# Spannungsversorgung.net
KiCad netlist of a schematic drawn in EAGLE
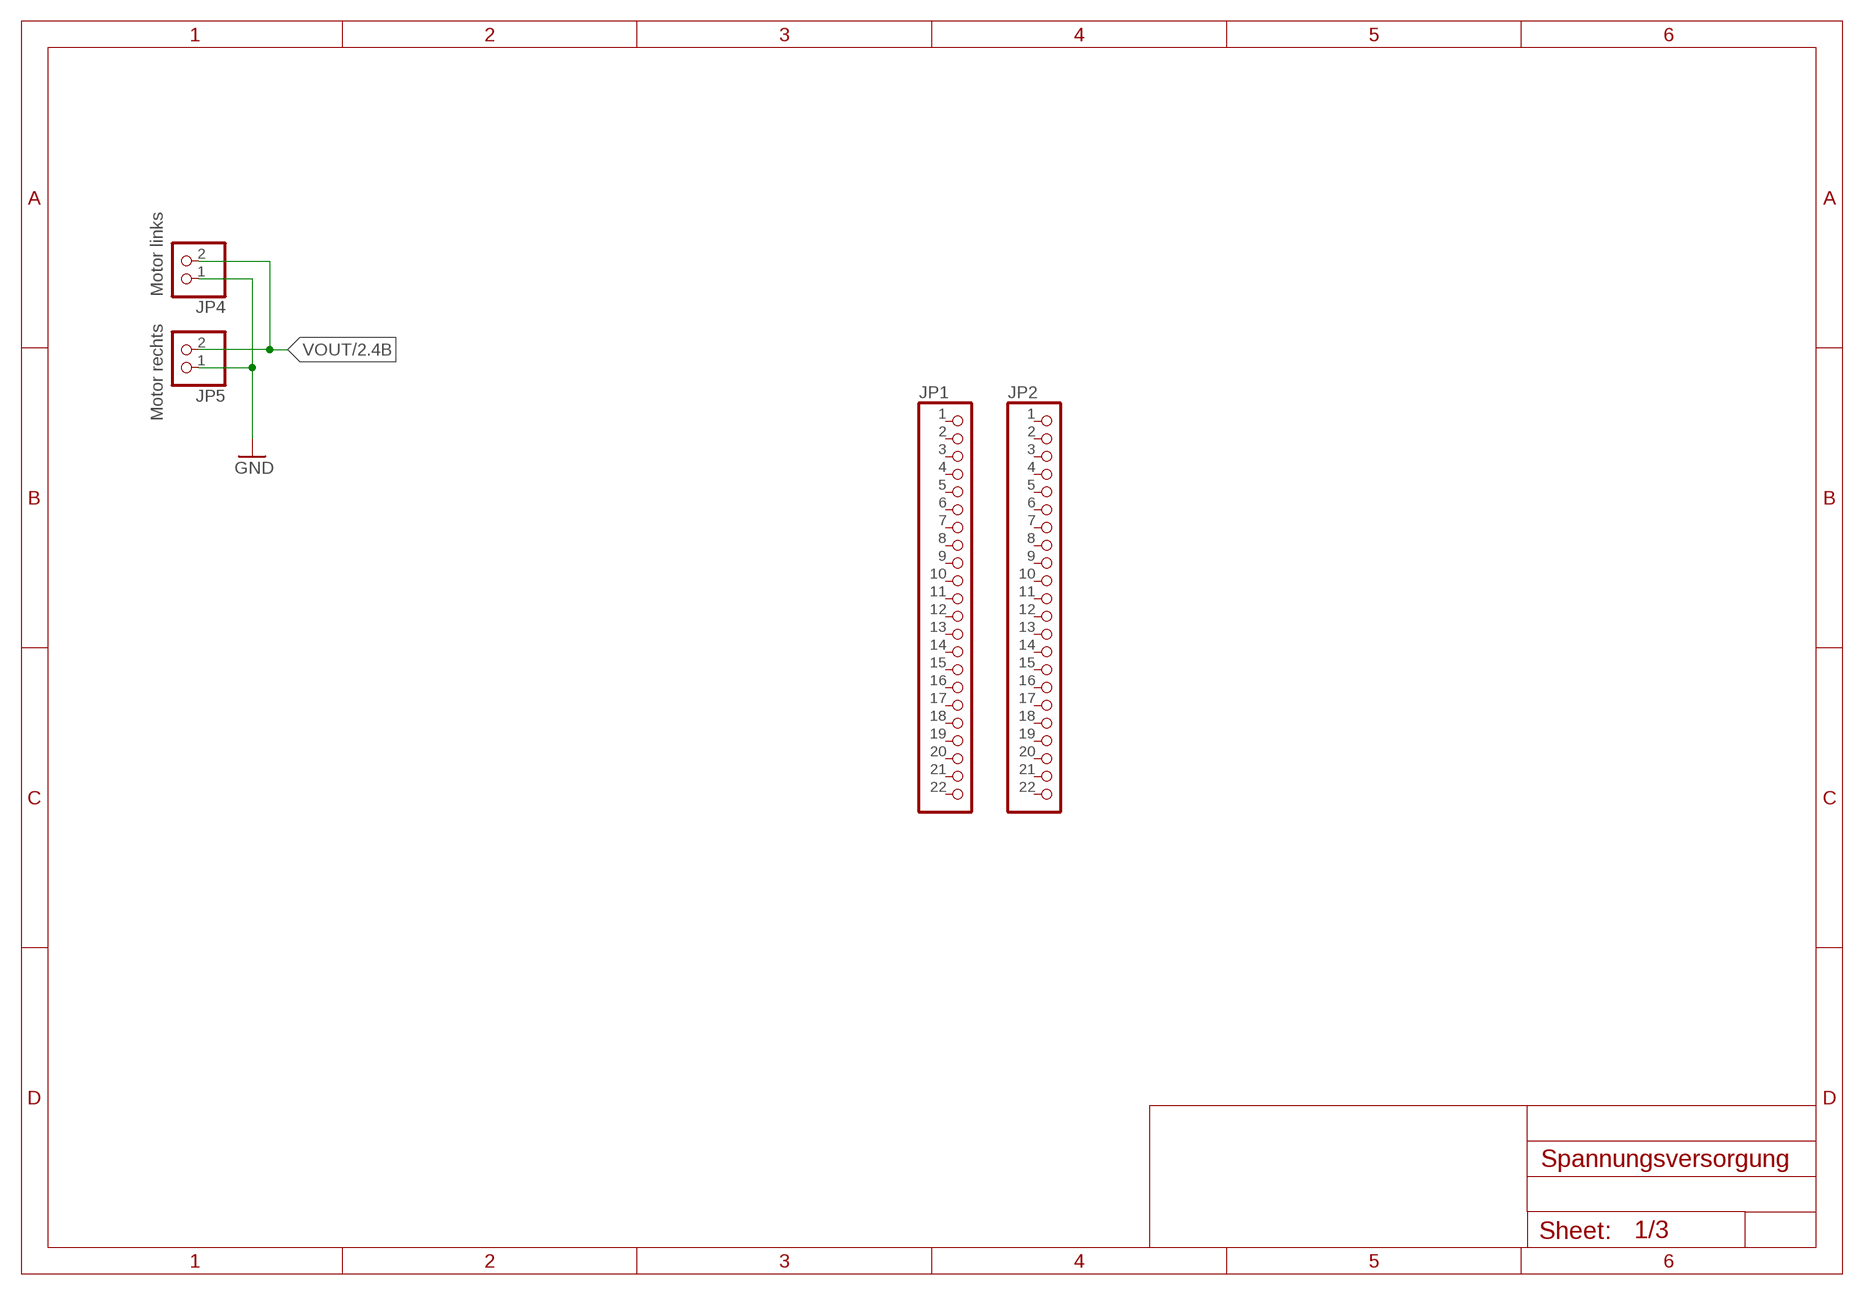
[diagram p0: schematic, sheet 1]
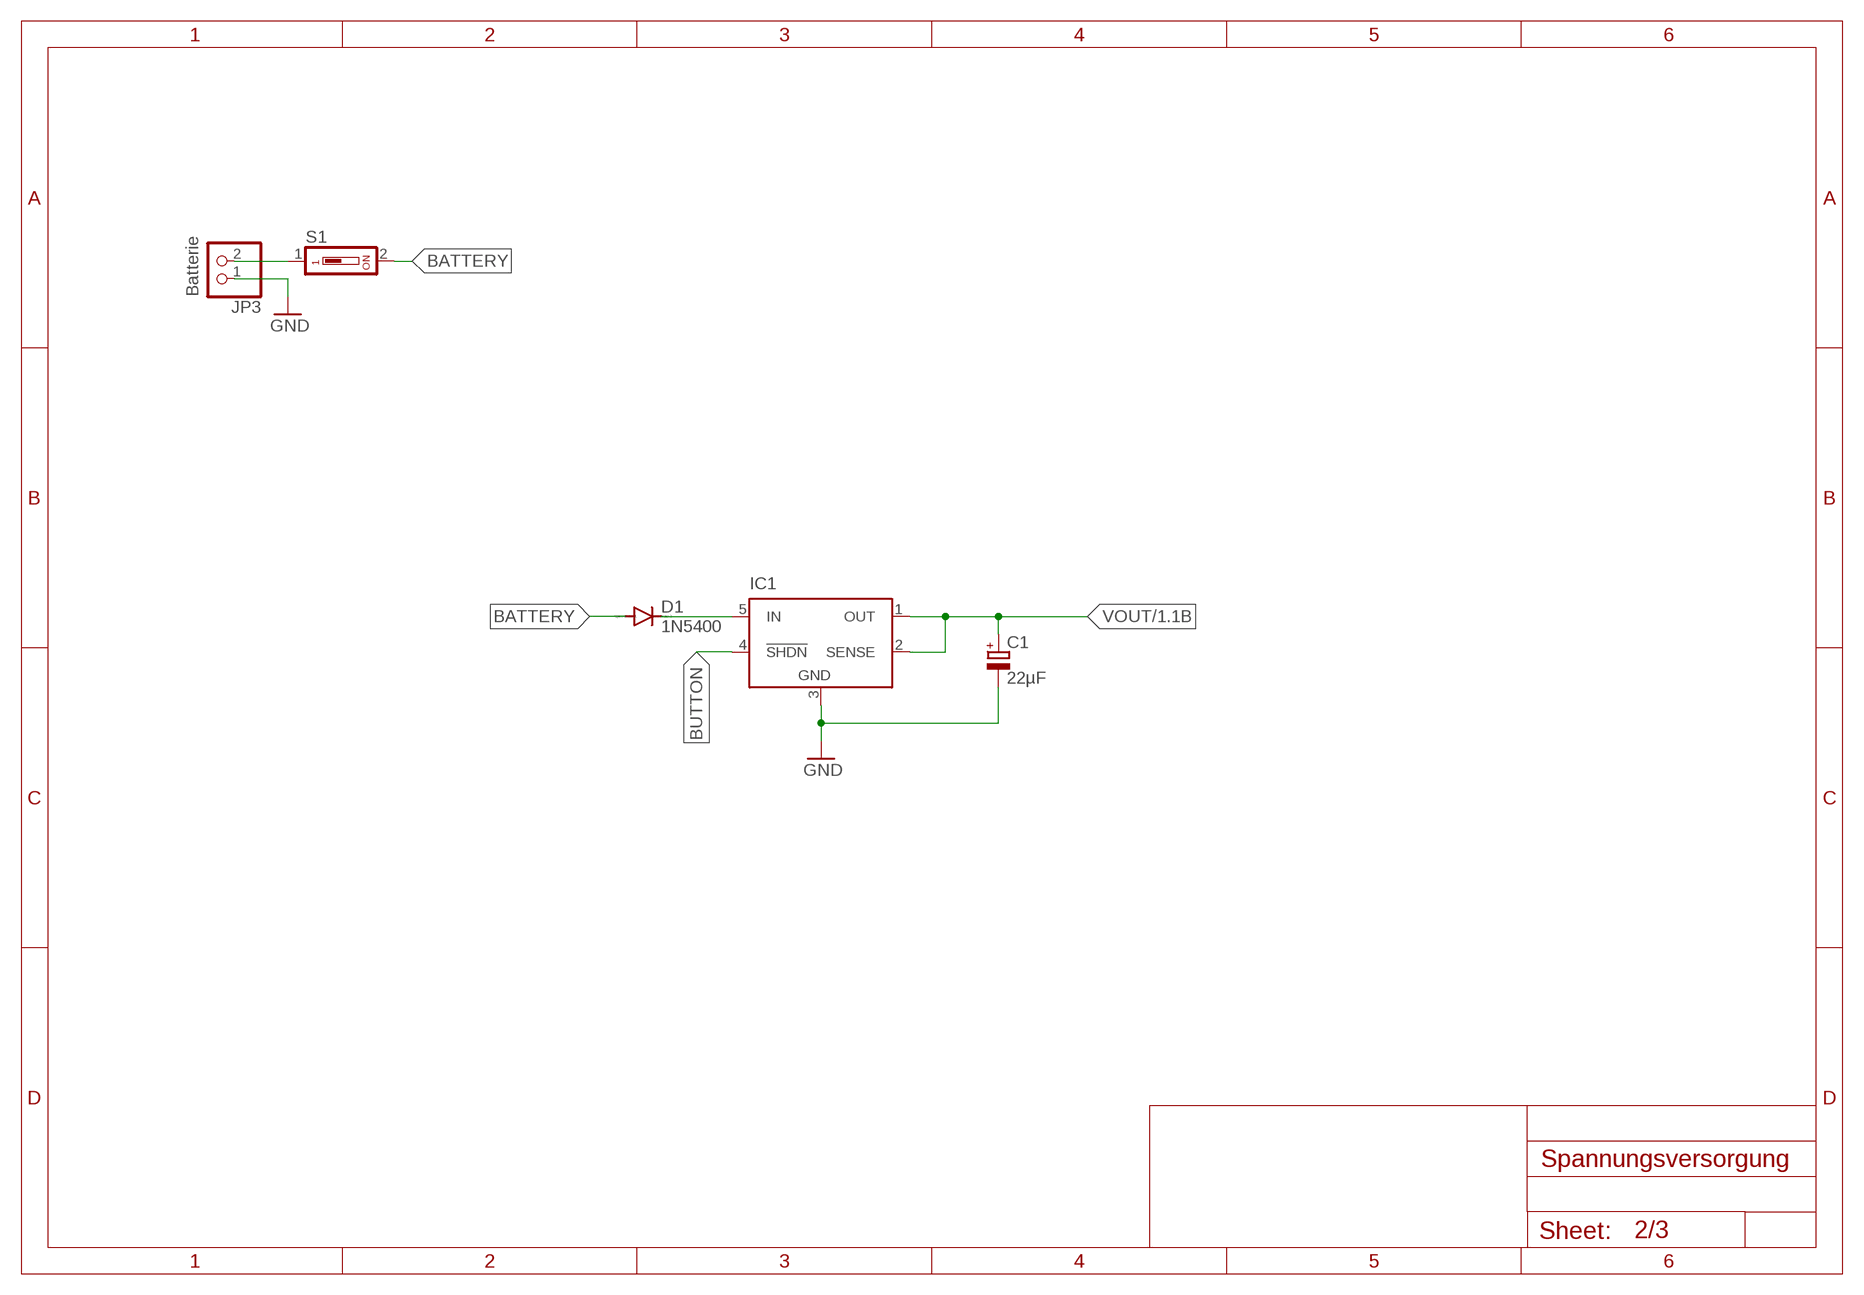
[diagram p1: schematic, sheet 2]
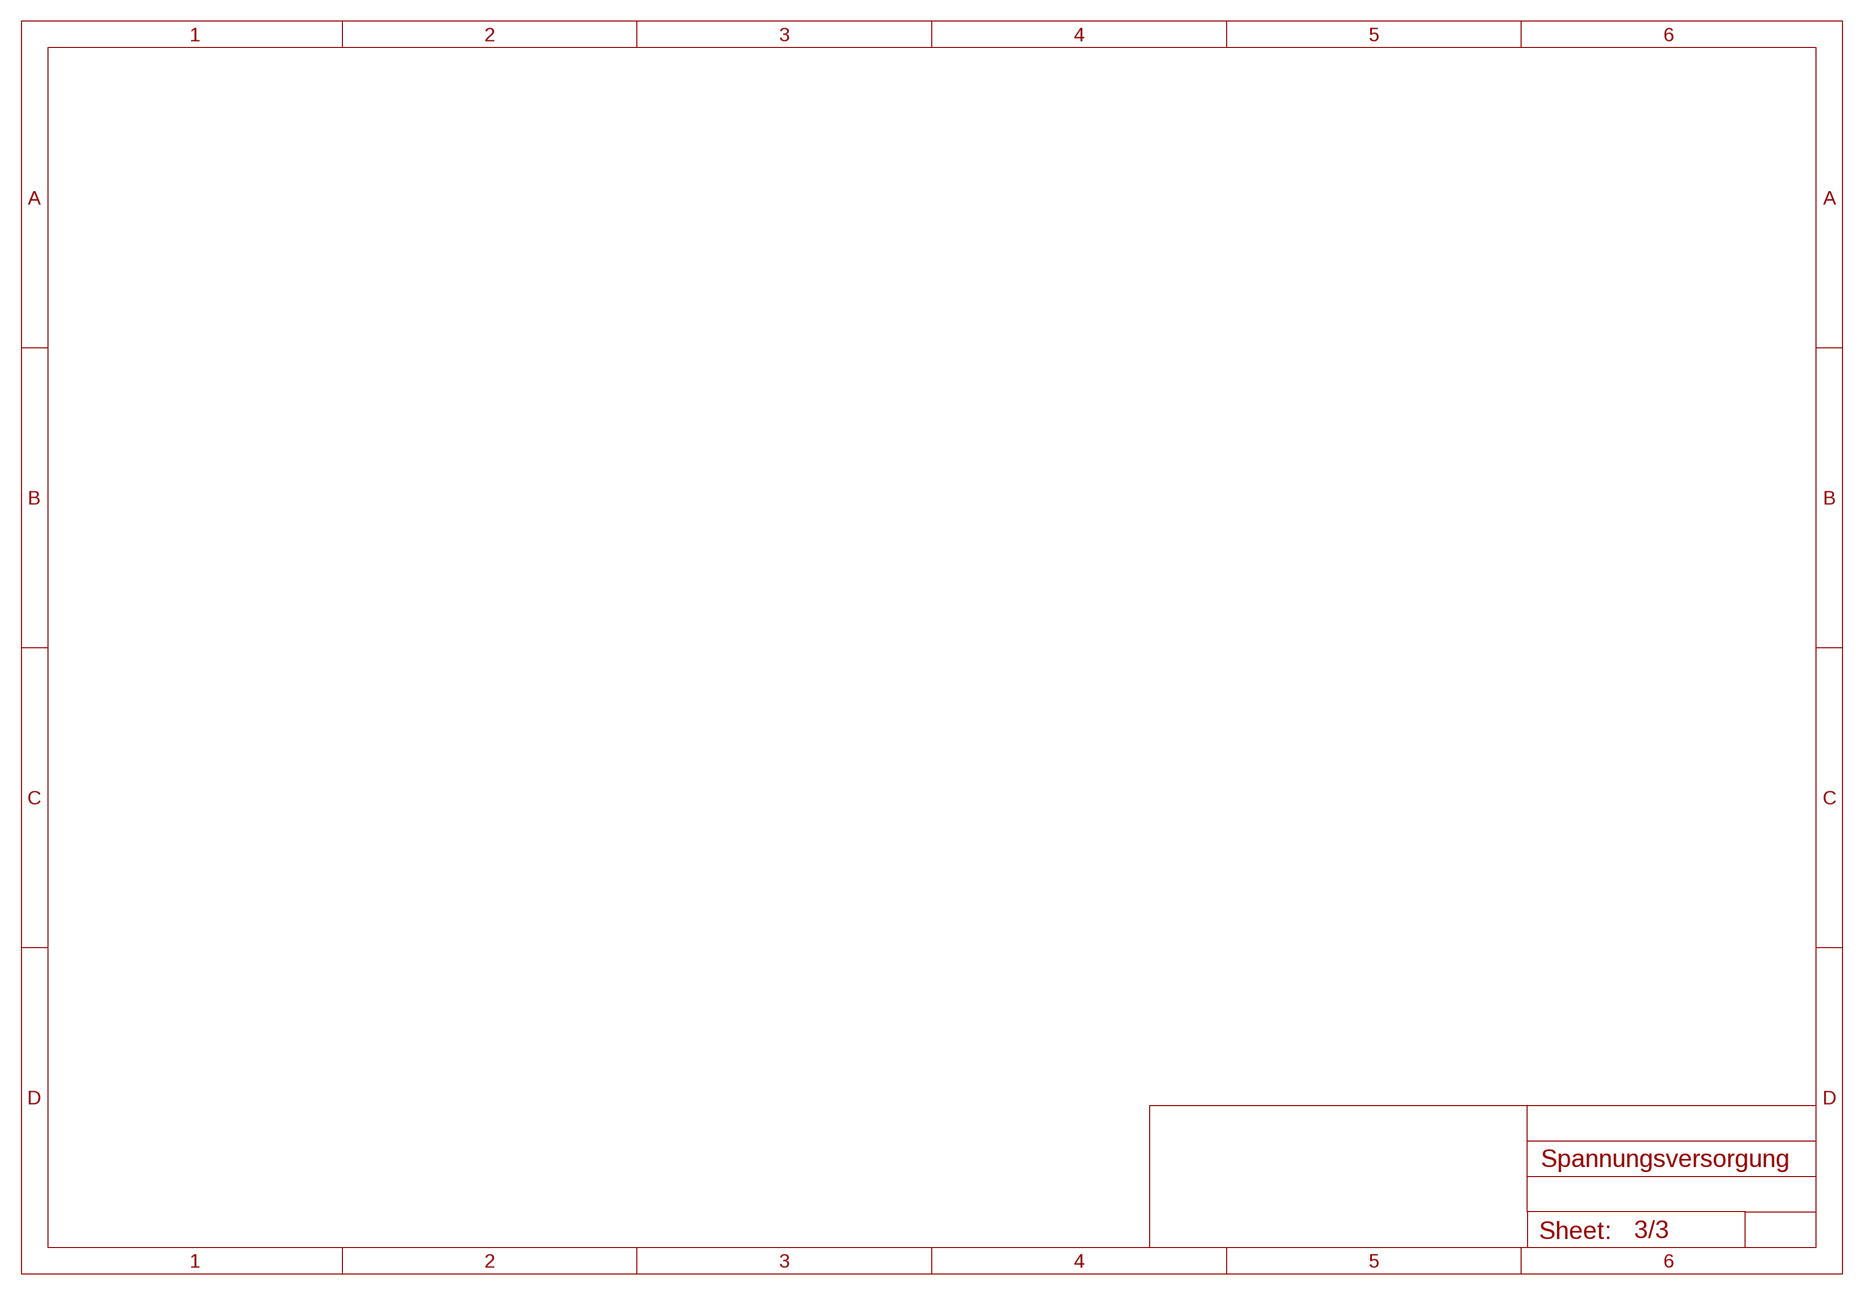
[diagram p2: schematic, sheet 3]

(export (version "E")
  (design (tool "Eeschema 10.0.6"))
  (components
    (comp (ref "JP1")
      (value "PINHD-1X22")
      (footprint "eagle-import:1X22")
      (libsource (lib "eagle-import") (part "PINHD-1X22"))
    )
    (comp (ref "JP2")
      (value "PINHD-1X22")
      (footprint "eagle-import:1X22")
      (libsource (lib "eagle-import") (part "PINHD-1X22"))
    )
    (comp (ref "JP4")
      (value "PINHD-1X2")
      (footprint "eagle-import:1X02")
      (libsource (lib "eagle-import") (part "PINHD-1X2"))
    )
    (comp (ref "JP5")
      (value "PINHD-1X2")
      (footprint "eagle-import:1X02")
      (libsource (lib "eagle-import") (part "PINHD-1X2"))
    )
    (comp (ref "C1")
      (value "22µF")
      (footprint "eagle-import:E2,5-5")
      (libsource (lib "eagle-import") (part "CPOL-EUE2.5-5"))
    )
    (comp (ref "D1")
      (value "1N5400")
      (footprint "eagle-import:DO201-15")
      (libsource (lib "eagle-import") (part "1N5400"))
    )
    (comp (ref "IC1")
      (value "LT1529T")
      (footprint "eagle-import:TO220-5")
      (libsource (lib "eagle-import") (part "LT1529T"))
    )
    (comp (ref "JP3")
      (value "PINHD-1X2")
      (footprint "eagle-import:1X02")
      (libsource (lib "eagle-import") (part "PINHD-1X2"))
    )
    (comp (ref "S1")
      (value "DS01")
      (footprint "eagle-import:DS-01")
      (libsource (lib "eagle-import") (part "DS01"))
    )
  )
  (nets
    (net (code "1") (name "BATTERY") (class "Default")
      (node (ref "D1") (pin "A") (pinfunction "A_A") (pintype "passive"))
      (node (ref "JP3") (pin "2") (pinfunction "2_2") (pintype "passive"))
      (node (ref "S1") (pin "1") (pinfunction "1_1") (pintype "passive"))
      (node (ref "S1") (pin "2") (pinfunction "2_2") (pintype "passive"))
    )
    (net (code "2") (name "BUTTON") (class "Default")
      (node (ref "IC1") (pin "4") (pinfunction "~{SHDN}_4") (pintype "input"))
    )
    (net (code "3") (name "GND") (class "Default")
      (node (ref "C1") (pin "-") (pinfunction "-_-") (pintype "passive"))
      (node (ref "IC1") (pin "3") (pinfunction "GND_3") (pintype "power_in"))
      (node (ref "JP3") (pin "1") (pinfunction "1_1") (pintype "passive"))
      (node (ref "JP4") (pin "1") (pinfunction "1_1") (pintype "passive"))
      (node (ref "JP5") (pin "1") (pinfunction "1_1") (pintype "passive"))
    )
    (net (code "4") (name "Net-(IC1-IN)") (class "Default")
      (node (ref "D1") (pin "C") (pinfunction "C_C") (pintype "passive"))
      (node (ref "IC1") (pin "5") (pinfunction "IN_5") (pintype "input"))
    )
    (net (code "5") (name "VOUT") (class "Default")
      (node (ref "C1") (pin "+") (pinfunction "+_+") (pintype "passive"))
      (node (ref "IC1") (pin "1") (pinfunction "OUT_1") (pintype "output"))
      (node (ref "IC1") (pin "2") (pinfunction "SENSE_2") (pintype "input"))
      (node (ref "JP4") (pin "2") (pinfunction "2_2") (pintype "passive"))
      (node (ref "JP5") (pin "2") (pinfunction "2_2") (pintype "passive"))
    )
    (net (code "6") (name "unconnected-(JP1-Pad1)") (class "Default")
      (node (ref "JP1") (pin "1") (pinfunction "1_1") (pintype "passive"))
    )
    (net (code "7") (name "unconnected-(JP1-Pad2)") (class "Default")
      (node (ref "JP1") (pin "2") (pinfunction "2_2") (pintype "passive"))
    )
    (net (code "8") (name "unconnected-(JP1-Pad3)") (class "Default")
      (node (ref "JP1") (pin "3") (pinfunction "3_3") (pintype "passive"))
    )
    (net (code "9") (name "unconnected-(JP1-Pad4)") (class "Default")
      (node (ref "JP1") (pin "4") (pinfunction "4_4") (pintype "passive"))
    )
    (net (code "10") (name "unconnected-(JP1-Pad5)") (class "Default")
      (node (ref "JP1") (pin "5") (pinfunction "5_5") (pintype "passive"))
    )
    (net (code "11") (name "unconnected-(JP1-Pad6)") (class "Default")
      (node (ref "JP1") (pin "6") (pinfunction "6_6") (pintype "passive"))
    )
    (net (code "12") (name "unconnected-(JP1-Pad7)") (class "Default")
      (node (ref "JP1") (pin "7") (pinfunction "7_7") (pintype "passive"))
    )
    (net (code "13") (name "unconnected-(JP1-Pad8)") (class "Default")
      (node (ref "JP1") (pin "8") (pinfunction "8_8") (pintype "passive"))
    )
    (net (code "14") (name "unconnected-(JP1-Pad9)") (class "Default")
      (node (ref "JP1") (pin "9") (pinfunction "9_9") (pintype "passive"))
    )
    (net (code "15") (name "unconnected-(JP1-Pad10)") (class "Default")
      (node (ref "JP1") (pin "10") (pinfunction "10_10") (pintype "passive"))
    )
    (net (code "16") (name "unconnected-(JP1-Pad11)") (class "Default")
      (node (ref "JP1") (pin "11") (pinfunction "11_11") (pintype "passive"))
    )
    (net (code "17") (name "unconnected-(JP1-Pad12)") (class "Default")
      (node (ref "JP1") (pin "12") (pinfunction "12_12") (pintype "passive"))
    )
    (net (code "18") (name "unconnected-(JP1-Pad13)") (class "Default")
      (node (ref "JP1") (pin "13") (pinfunction "13_13") (pintype "passive"))
    )
    (net (code "19") (name "unconnected-(JP1-Pad14)") (class "Default")
      (node (ref "JP1") (pin "14") (pinfunction "14_14") (pintype "passive"))
    )
    (net (code "20") (name "unconnected-(JP1-Pad15)") (class "Default")
      (node (ref "JP1") (pin "15") (pinfunction "15_15") (pintype "passive"))
    )
    (net (code "21") (name "unconnected-(JP1-Pad16)") (class "Default")
      (node (ref "JP1") (pin "16") (pinfunction "16_16") (pintype "passive"))
    )
    (net (code "22") (name "unconnected-(JP1-Pad17)") (class "Default")
      (node (ref "JP1") (pin "17") (pinfunction "17_17") (pintype "passive"))
    )
    (net (code "23") (name "unconnected-(JP1-Pad18)") (class "Default")
      (node (ref "JP1") (pin "18") (pinfunction "18_18") (pintype "passive"))
    )
    (net (code "24") (name "unconnected-(JP1-Pad19)") (class "Default")
      (node (ref "JP1") (pin "19") (pinfunction "19_19") (pintype "passive"))
    )
    (net (code "25") (name "unconnected-(JP1-Pad20)") (class "Default")
      (node (ref "JP1") (pin "20") (pinfunction "20_20") (pintype "passive"))
    )
    (net (code "26") (name "unconnected-(JP1-Pad21)") (class "Default")
      (node (ref "JP1") (pin "21") (pinfunction "21_21") (pintype "passive"))
    )
    (net (code "27") (name "unconnected-(JP1-Pad22)") (class "Default")
      (node (ref "JP1") (pin "22") (pinfunction "22_22") (pintype "passive"))
    )
    (net (code "28") (name "unconnected-(JP2-Pad1)") (class "Default")
      (node (ref "JP2") (pin "1") (pinfunction "1_1") (pintype "passive"))
    )
    (net (code "29") (name "unconnected-(JP2-Pad2)") (class "Default")
      (node (ref "JP2") (pin "2") (pinfunction "2_2") (pintype "passive"))
    )
    (net (code "30") (name "unconnected-(JP2-Pad3)") (class "Default")
      (node (ref "JP2") (pin "3") (pinfunction "3_3") (pintype "passive"))
    )
    (net (code "31") (name "unconnected-(JP2-Pad4)") (class "Default")
      (node (ref "JP2") (pin "4") (pinfunction "4_4") (pintype "passive"))
    )
    (net (code "32") (name "unconnected-(JP2-Pad5)") (class "Default")
      (node (ref "JP2") (pin "5") (pinfunction "5_5") (pintype "passive"))
    )
    (net (code "33") (name "unconnected-(JP2-Pad6)") (class "Default")
      (node (ref "JP2") (pin "6") (pinfunction "6_6") (pintype "passive"))
    )
    (net (code "34") (name "unconnected-(JP2-Pad7)") (class "Default")
      (node (ref "JP2") (pin "7") (pinfunction "7_7") (pintype "passive"))
    )
    (net (code "35") (name "unconnected-(JP2-Pad8)") (class "Default")
      (node (ref "JP2") (pin "8") (pinfunction "8_8") (pintype "passive"))
    )
    (net (code "36") (name "unconnected-(JP2-Pad9)") (class "Default")
      (node (ref "JP2") (pin "9") (pinfunction "9_9") (pintype "passive"))
    )
    (net (code "37") (name "unconnected-(JP2-Pad10)") (class "Default")
      (node (ref "JP2") (pin "10") (pinfunction "10_10") (pintype "passive"))
    )
    (net (code "38") (name "unconnected-(JP2-Pad11)") (class "Default")
      (node (ref "JP2") (pin "11") (pinfunction "11_11") (pintype "passive"))
    )
    (net (code "39") (name "unconnected-(JP2-Pad12)") (class "Default")
      (node (ref "JP2") (pin "12") (pinfunction "12_12") (pintype "passive"))
    )
    (net (code "40") (name "unconnected-(JP2-Pad13)") (class "Default")
      (node (ref "JP2") (pin "13") (pinfunction "13_13") (pintype "passive"))
    )
    (net (code "41") (name "unconnected-(JP2-Pad14)") (class "Default")
      (node (ref "JP2") (pin "14") (pinfunction "14_14") (pintype "passive"))
    )
    (net (code "42") (name "unconnected-(JP2-Pad15)") (class "Default")
      (node (ref "JP2") (pin "15") (pinfunction "15_15") (pintype "passive"))
    )
    (net (code "43") (name "unconnected-(JP2-Pad16)") (class "Default")
      (node (ref "JP2") (pin "16") (pinfunction "16_16") (pintype "passive"))
    )
    (net (code "44") (name "unconnected-(JP2-Pad17)") (class "Default")
      (node (ref "JP2") (pin "17") (pinfunction "17_17") (pintype "passive"))
    )
    (net (code "45") (name "unconnected-(JP2-Pad18)") (class "Default")
      (node (ref "JP2") (pin "18") (pinfunction "18_18") (pintype "passive"))
    )
    (net (code "46") (name "unconnected-(JP2-Pad19)") (class "Default")
      (node (ref "JP2") (pin "19") (pinfunction "19_19") (pintype "passive"))
    )
    (net (code "47") (name "unconnected-(JP2-Pad20)") (class "Default")
      (node (ref "JP2") (pin "20") (pinfunction "20_20") (pintype "passive"))
    )
    (net (code "48") (name "unconnected-(JP2-Pad21)") (class "Default")
      (node (ref "JP2") (pin "21") (pinfunction "21_21") (pintype "passive"))
    )
    (net (code "49") (name "unconnected-(JP2-Pad22)") (class "Default")
      (node (ref "JP2") (pin "22") (pinfunction "22_22") (pintype "passive"))
    )
  )
)
